# SNESModule_r2.net
KiCad netlist of a schematic drawn in EAGLE
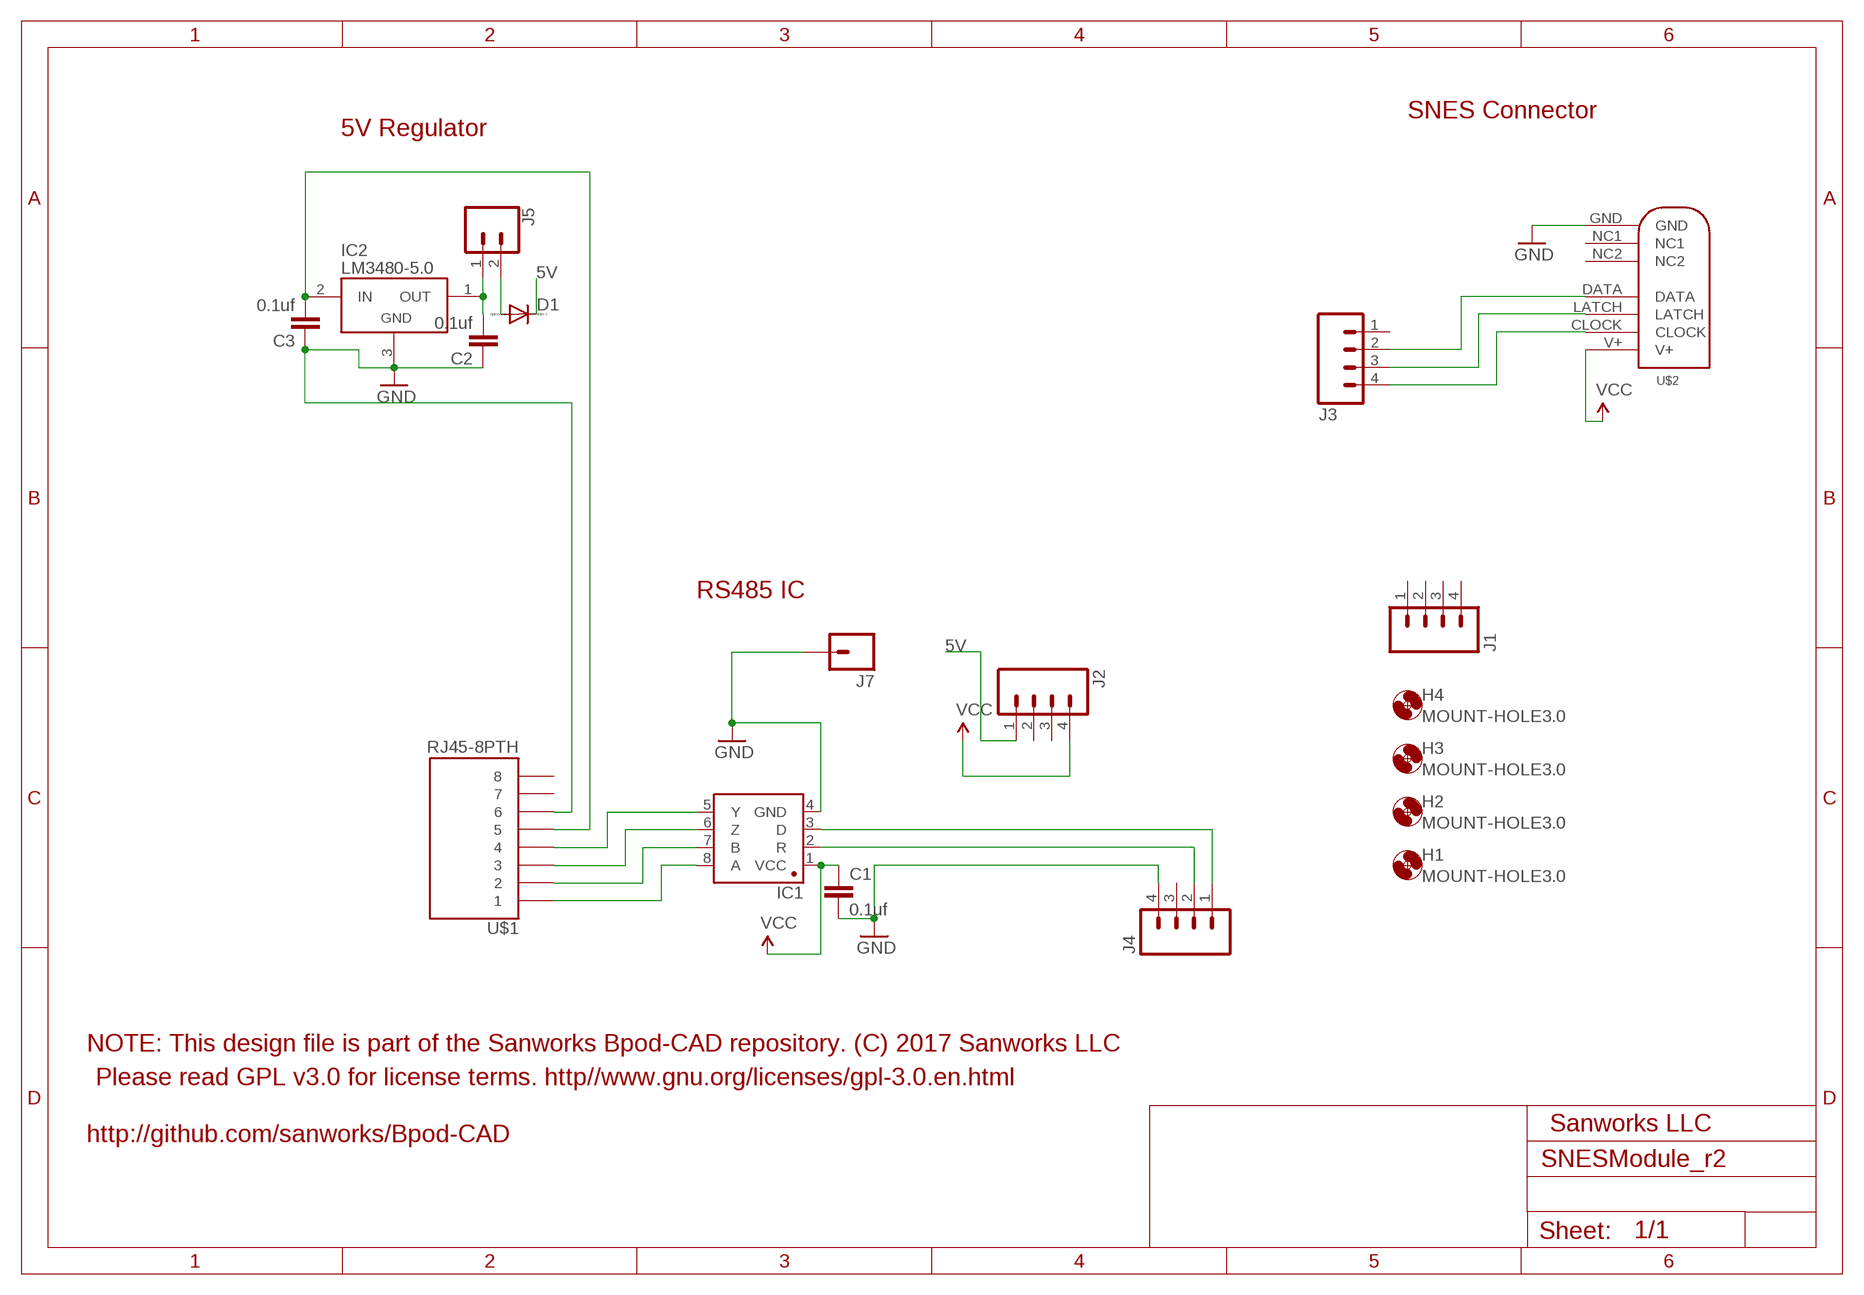
[diagram p0: schematic, sheet 1]

(export (version "E")
  (design (tool "Eeschema 10.0.6"))
  (components
    (comp (ref "C1")
      (value "0.1uf")
      (footprint "eagle-import:1206")
      (libsource (lib "eagle-import") (part "CAP1206"))
    )
    (comp (ref "C2")
      (value "0.1uf")
      (footprint "eagle-import:1206")
      (libsource (lib "eagle-import") (part "CAP1206"))
    )
    (comp (ref "C3")
      (value "0.1uf")
      (footprint "eagle-import:1206")
      (libsource (lib "eagle-import") (part "CAP1206"))
    )
    (comp (ref "D1")
      (value "MBR0520LT")
      (footprint "eagle-import:SOD123")
      (libsource (lib "eagle-import") (part "MBR0520LT"))
    )
    (comp (ref "H1")
      (value "MOUNT-HOLE3.0")
      (footprint "eagle-import:3,0")
      (libsource (lib "eagle-import") (part "MOUNT-HOLE3.0"))
    )
    (comp (ref "H2")
      (value "MOUNT-HOLE3.0")
      (footprint "eagle-import:3,0")
      (libsource (lib "eagle-import") (part "MOUNT-HOLE3.0"))
    )
    (comp (ref "H3")
      (value "MOUNT-HOLE3.0")
      (footprint "eagle-import:3,0")
      (libsource (lib "eagle-import") (part "MOUNT-HOLE3.0"))
    )
    (comp (ref "H4")
      (value "MOUNT-HOLE3.0")
      (footprint "eagle-import:3,0")
      (libsource (lib "eagle-import") (part "MOUNT-HOLE3.0"))
    )
    (comp (ref "IC1")
      (value "SN65HVD31DR")
      (footprint "eagle-import:SO08")
      (libsource (lib "eagle-import") (part "SN65HVD31DR"))
    )
    (comp (ref "IC2")
      (value "LM3480-5.0")
      (footprint "eagle-import:SOT-23-3")
      (libsource (lib "eagle-import") (part "LM3480-5.0"))
    )
    (comp (ref "J1")
      (value "M04PTH")
      (footprint "eagle-import:1X04")
      (libsource (lib "eagle-import") (part "M04PTH"))
    )
    (comp (ref "J2")
      (value "M04PTH")
      (footprint "eagle-import:1X04")
      (libsource (lib "eagle-import") (part "M04PTH"))
    )
    (comp (ref "J3")
      (value "M04PTH")
      (footprint "eagle-import:1X04")
      (libsource (lib "eagle-import") (part "M04PTH"))
    )
    (comp (ref "J4")
      (value "M04PTH")
      (footprint "eagle-import:1X04")
      (libsource (lib "eagle-import") (part "M04PTH"))
    )
    (comp (ref "J5")
      (value "CONN_02")
      (footprint "eagle-import:1X02")
      (libsource (lib "eagle-import") (part "CONN_02"))
    )
    (comp (ref "J7")
      (value "M01PTH")
      (footprint "eagle-import:1X01")
      (libsource (lib "eagle-import") (part "M01PTH"))
    )
    (comp (ref "U$1")
      (value "RJ45-8PTH")
      (footprint "eagle-import:RJ45-8")
      (libsource (lib "eagle-import") (part "RJ45-8PTH"))
    )
    (comp (ref "U$2")
      (value "SNES_CONNECTOR")
      (footprint "eagle-import:SNES_CONNECTOR")
      (libsource (lib "eagle-import") (part "SNES_CONNECTOR"))
    )
  )
  (nets
    (net (code "1") (name "/5V") (class "Default")
      (node (ref "D1") (pin "C") (pinfunction "C_C") (pintype "passive"))
      (node (ref "J2") (pin "1") (pinfunction "1_1") (pintype "passive"))
    )
    (net (code "2") (name "GND") (class "Default")
      (node (ref "C1") (pin "2") (pinfunction "2_2") (pintype "passive"))
      (node (ref "C2") (pin "1") (pinfunction "1_1") (pintype "passive"))
      (node (ref "C3") (pin "1") (pinfunction "1_1") (pintype "passive"))
      (node (ref "IC1") (pin "4") (pinfunction "GND_4") (pintype "bidirectional"))
      (node (ref "IC2") (pin "3") (pinfunction "GND_3") (pintype "power_in"))
      (node (ref "J4") (pin "4") (pinfunction "4_4") (pintype "passive"))
      (node (ref "J7") (pin "1") (pinfunction "1_1") (pintype "passive"))
      (node (ref "U$1") (pin "6") (pinfunction "6_6") (pintype "bidirectional"))
      (node (ref "U$2") (pin "GND") (pinfunction "GND_GND") (pintype "passive"))
    )
    (net (code "3") (name "Net-(D1-PadA)") (class "Default")
      (node (ref "D1") (pin "A") (pinfunction "A_A") (pintype "passive"))
      (node (ref "J5") (pin "2") (pinfunction "2_2") (pintype "passive"))
    )
    (net (code "4") (name "Net-(IC1-A)") (class "Default")
      (node (ref "IC1") (pin "8") (pinfunction "A_8") (pintype "bidirectional"))
      (node (ref "U$1") (pin "1") (pinfunction "1_1") (pintype "bidirectional"))
    )
    (net (code "5") (name "Net-(IC1-B)") (class "Default")
      (node (ref "IC1") (pin "7") (pinfunction "B_7") (pintype "bidirectional"))
      (node (ref "U$1") (pin "2") (pinfunction "2_2") (pintype "bidirectional"))
    )
    (net (code "6") (name "Net-(IC1-D)") (class "Default")
      (node (ref "IC1") (pin "3") (pinfunction "D_3") (pintype "bidirectional"))
      (node (ref "J4") (pin "1") (pinfunction "1_1") (pintype "passive"))
    )
    (net (code "7") (name "Net-(IC1-R)") (class "Default")
      (node (ref "IC1") (pin "2") (pinfunction "R_2") (pintype "bidirectional"))
      (node (ref "J4") (pin "2") (pinfunction "2_2") (pintype "passive"))
    )
    (net (code "8") (name "Net-(IC1-Y)") (class "Default")
      (node (ref "IC1") (pin "5") (pinfunction "Y_5") (pintype "bidirectional"))
      (node (ref "U$1") (pin "4") (pinfunction "4_4") (pintype "bidirectional"))
    )
    (net (code "9") (name "Net-(IC1-Z)") (class "Default")
      (node (ref "IC1") (pin "6") (pinfunction "Z_6") (pintype "bidirectional"))
      (node (ref "U$1") (pin "3") (pinfunction "3_3") (pintype "bidirectional"))
    )
    (net (code "10") (name "Net-(IC2-IN)") (class "Default")
      (node (ref "C3") (pin "2") (pinfunction "2_2") (pintype "passive"))
      (node (ref "IC2") (pin "2") (pinfunction "IN_2") (pintype "power_in"))
      (node (ref "U$1") (pin "5") (pinfunction "5_5") (pintype "bidirectional"))
    )
    (net (code "11") (name "Net-(IC2-OUT)") (class "Default")
      (node (ref "C2") (pin "2") (pinfunction "2_2") (pintype "passive"))
      (node (ref "IC2") (pin "1") (pinfunction "OUT_1") (pintype "power_in"))
      (node (ref "J5") (pin "1") (pinfunction "1_1") (pintype "passive"))
    )
    (net (code "12") (name "Net-(J3-Pad2)") (class "Default")
      (node (ref "J3") (pin "2") (pinfunction "2_2") (pintype "passive"))
      (node (ref "U$2") (pin "DATA") (pinfunction "DATA_DATA") (pintype "passive"))
    )
    (net (code "13") (name "Net-(J3-Pad3)") (class "Default")
      (node (ref "J3") (pin "3") (pinfunction "3_3") (pintype "passive"))
      (node (ref "U$2") (pin "LATCH") (pinfunction "LATCH_LATCH") (pintype "passive"))
    )
    (net (code "14") (name "Net-(J3-Pad4)") (class "Default")
      (node (ref "J3") (pin "4") (pinfunction "4_4") (pintype "passive"))
      (node (ref "U$2") (pin "CLOCK") (pinfunction "CLOCK_CLOCK") (pintype "passive"))
    )
    (net (code "15") (name "VCC") (class "Default")
      (node (ref "C1") (pin "1") (pinfunction "1_1") (pintype "passive"))
      (node (ref "IC1") (pin "1") (pinfunction "VCC_1") (pintype "bidirectional"))
      (node (ref "J2") (pin "4") (pinfunction "4_4") (pintype "passive"))
      (node (ref "U$2") (pin "V+") (pinfunction "V+_V+") (pintype "passive"))
    )
    (net (code "16") (name "unconnected-(J1-Pad1)") (class "Default")
      (node (ref "J1") (pin "1") (pinfunction "1_1") (pintype "passive"))
    )
    (net (code "17") (name "unconnected-(J1-Pad2)") (class "Default")
      (node (ref "J1") (pin "2") (pinfunction "2_2") (pintype "passive"))
    )
    (net (code "18") (name "unconnected-(J1-Pad3)") (class "Default")
      (node (ref "J1") (pin "3") (pinfunction "3_3") (pintype "passive"))
    )
    (net (code "19") (name "unconnected-(J1-Pad4)") (class "Default")
      (node (ref "J1") (pin "4") (pinfunction "4_4") (pintype "passive"))
    )
    (net (code "20") (name "unconnected-(J2-Pad2)") (class "Default")
      (node (ref "J2") (pin "2") (pinfunction "2_2") (pintype "passive"))
    )
    (net (code "21") (name "unconnected-(J2-Pad3)") (class "Default")
      (node (ref "J2") (pin "3") (pinfunction "3_3") (pintype "passive"))
    )
    (net (code "22") (name "unconnected-(J3-Pad1)") (class "Default")
      (node (ref "J3") (pin "1") (pinfunction "1_1") (pintype "passive"))
    )
    (net (code "23") (name "unconnected-(J4-Pad3)") (class "Default")
      (node (ref "J4") (pin "3") (pinfunction "3_3") (pintype "passive"))
    )
    (net (code "24") (name "unconnected-(U$1-Pad7)") (class "Default")
      (node (ref "U$1") (pin "7") (pinfunction "7_7") (pintype "bidirectional"))
    )
    (net (code "25") (name "unconnected-(U$1-Pad8)") (class "Default")
      (node (ref "U$1") (pin "8") (pinfunction "8_8") (pintype "bidirectional"))
    )
    (net (code "26") (name "unconnected-(U$2-PadNC1)") (class "Default")
      (node (ref "U$2") (pin "NC1") (pinfunction "NC1_NC1") (pintype "passive"))
    )
    (net (code "27") (name "unconnected-(U$2-PadNC2)") (class "Default")
      (node (ref "U$2") (pin "NC2") (pinfunction "NC2_NC2") (pintype "passive"))
    )
  )
)
